# IO_Extension.net
KiCad netlist of a schematic drawn in Altium Designer
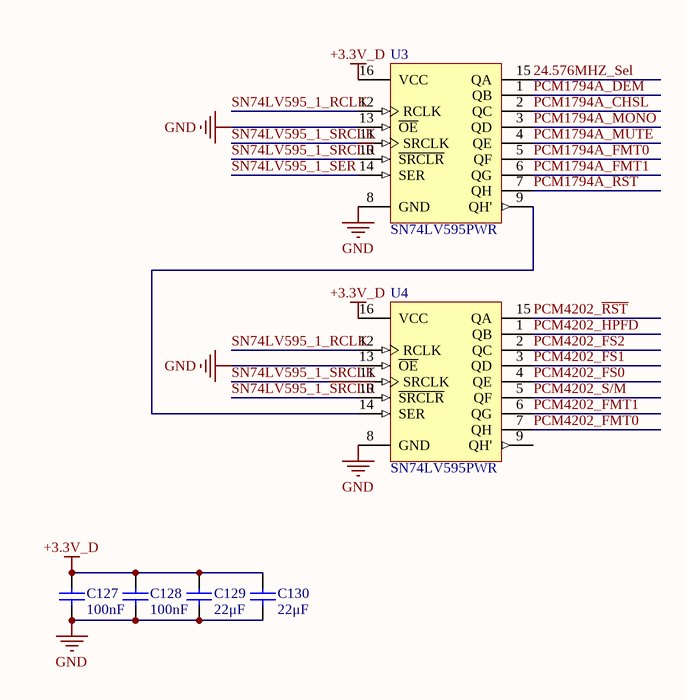
[diagram p0: IO_Extension.SchDoc]

(export (version "E")
  (design (tool "Eeschema 10.0.6"))
  (components
    (comp (ref "C127")
      (value "100nF")
      (footprint "C 0402_L")
      (description "Capacitor")
      (fields (field (name "PUBLISHER") "Altium Limited"))
      (libsource (lib "Miscellaneous Devices") (part "Cap"))
    )
    (comp (ref "C128")
      (value "100nF")
      (footprint "C 0402_L")
      (description "Capacitor")
      (fields (field (name "PUBLISHER") "Altium Limited"))
      (libsource (lib "Miscellaneous Devices") (part "Cap"))
    )
    (comp (ref "C129")
      (value "22μF")
      (footprint "0805_C")
      (description "Capacitor")
      (fields (field (name "PUBLISHER") "Altium Limited"))
      (libsource (lib "Miscellaneous Devices") (part "Cap"))
    )
    (comp (ref "C130")
      (value "22μF")
      (footprint "0805_C")
      (description "Capacitor")
      (fields (field (name "PUBLISHER") "Altium Limited"))
      (libsource (lib "Miscellaneous Devices") (part "Cap"))
    )
    (comp (ref "U3")
      (value "SN74LV595PWR")
      (footprint "PW0016A_L")
      (description "8-Bit Shift Registers With 3-State Output Registers, PW0016A, LARGE T&R")
      (fields
        (field (name "GENERIC PART NUMBER") "SN74AHC595")
        (field (name "MANUFACTURER") "Texas Instruments")
      )
      (libsource (lib "SN74LV595") (part "CMP-0807-00193-3"))
    )
    (comp (ref "U4")
      (value "SN74LV595PWR")
      (footprint "PW0016A_L")
      (description "8-Bit Shift Registers With 3-State Output Registers, PW0016A, LARGE T&R")
      (fields
        (field (name "GENERIC PART NUMBER") "SN74AHC595")
        (field (name "MANUFACTURER") "Texas Instruments")
      )
      (libsource (lib "SN74LV595") (part "CMP-0807-00193-3"))
    )
  )
  (nets
    (net (code "1") (name "+3.3V_D") (class "Default")
      (node (ref "C127") (pin "1") (pinfunction "1_1") (pintype "passive"))
      (node (ref "C128") (pin "1") (pinfunction "1_1") (pintype "passive"))
      (node (ref "C129") (pin "1") (pinfunction "1_1") (pintype "passive"))
      (node (ref "C130") (pin "1") (pinfunction "1_1") (pintype "passive"))
      (node (ref "U3") (pin "16") (pinfunction "VCC_16") (pintype "power_in"))
      (node (ref "U4") (pin "16") (pinfunction "VCC_16") (pintype "power_in"))
    )
    (net (code "2") (name "/24.576MHZ_Sel") (class "Default")
      (node (ref "U3") (pin "15") (pinfunction "QA_15") (pintype "tri_state"))
    )
    (net (code "3") (name "/PCM1794A_CHSL") (class "Default")
      (node (ref "U3") (pin "2") (pinfunction "QC_2") (pintype "tri_state"))
    )
    (net (code "4") (name "/PCM1794A_DEM") (class "Default")
      (node (ref "U3") (pin "1") (pinfunction "QB_1") (pintype "tri_state"))
    )
    (net (code "5") (name "/PCM1794A_FMT0") (class "Default")
      (node (ref "U3") (pin "5") (pinfunction "QF_5") (pintype "tri_state"))
    )
    (net (code "6") (name "/PCM1794A_FMT1") (class "Default")
      (node (ref "U3") (pin "6") (pinfunction "QG_6") (pintype "tri_state"))
    )
    (net (code "7") (name "/PCM1794A_MONO") (class "Default")
      (node (ref "U3") (pin "3") (pinfunction "QD_3") (pintype "tri_state"))
    )
    (net (code "8") (name "/PCM1794A_MUTE") (class "Default")
      (node (ref "U3") (pin "4") (pinfunction "QE_4") (pintype "tri_state"))
    )
    (net (code "9") (name "/PCM1794A_~{RST}") (class "Default")
      (node (ref "U3") (pin "7") (pinfunction "QH_7") (pintype "tri_state"))
    )
    (net (code "10") (name "/PCM4202_FMT0") (class "Default")
      (node (ref "U4") (pin "7") (pinfunction "QH_7") (pintype "tri_state"))
    )
    (net (code "11") (name "/PCM4202_FMT1") (class "Default")
      (node (ref "U4") (pin "6") (pinfunction "QG_6") (pintype "tri_state"))
    )
    (net (code "12") (name "/PCM4202_FS0") (class "Default")
      (node (ref "U4") (pin "4") (pinfunction "QE_4") (pintype "tri_state"))
    )
    (net (code "13") (name "/PCM4202_FS1") (class "Default")
      (node (ref "U4") (pin "3") (pinfunction "QD_3") (pintype "tri_state"))
    )
    (net (code "14") (name "/PCM4202_FS2") (class "Default")
      (node (ref "U4") (pin "2") (pinfunction "QC_2") (pintype "tri_state"))
    )
    (net (code "15") (name "/PCM4202_HPFD") (class "Default")
      (node (ref "U4") (pin "1") (pinfunction "QB_1") (pintype "tri_state"))
    )
    (net (code "16") (name "/PCM4202_S{slash}~{M}") (class "Default")
      (node (ref "U4") (pin "5") (pinfunction "QF_5") (pintype "tri_state"))
    )
    (net (code "17") (name "/PCM4202_~{RST}") (class "Default")
      (node (ref "U4") (pin "15") (pinfunction "QA_15") (pintype "tri_state"))
    )
    (net (code "18") (name "/SN74LV595_1_RCLK") (class "Default")
      (node (ref "U3") (pin "12") (pinfunction "RCLK_12") (pintype "input"))
      (node (ref "U4") (pin "12") (pinfunction "RCLK_12") (pintype "input"))
    )
    (net (code "19") (name "/SN74LV595_1_SER") (class "Default")
      (node (ref "U3") (pin "14") (pinfunction "SER_14") (pintype "input"))
    )
    (net (code "20") (name "/SN74LV595_1_SRCLK") (class "Default")
      (node (ref "U3") (pin "11") (pinfunction "SRCLK_11") (pintype "input"))
      (node (ref "U4") (pin "11") (pinfunction "SRCLK_11") (pintype "input"))
    )
    (net (code "21") (name "/SN74LV595_1_~{SRCLR}") (class "Default")
      (node (ref "U3") (pin "10") (pinfunction "~{SRCLR}_10") (pintype "input"))
      (node (ref "U4") (pin "10") (pinfunction "~{SRCLR}_10") (pintype "input"))
    )
    (net (code "22") (name "GND") (class "Default")
      (node (ref "C127") (pin "2") (pinfunction "2_2") (pintype "passive"))
      (node (ref "C128") (pin "2") (pinfunction "2_2") (pintype "passive"))
      (node (ref "C129") (pin "2") (pinfunction "2_2") (pintype "passive"))
      (node (ref "C130") (pin "2") (pinfunction "2_2") (pintype "passive"))
      (node (ref "U3") (pin "13") (pinfunction "~{OE}_13") (pintype "input"))
      (node (ref "U3") (pin "8") (pinfunction "GND_8") (pintype "power_in"))
      (node (ref "U4") (pin "13") (pinfunction "~{OE}_13") (pintype "input"))
      (node (ref "U4") (pin "8") (pinfunction "GND_8") (pintype "power_in"))
    )
    (net (code "23") (name "Net-(U3-QH')") (class "Default")
      (node (ref "U3") (pin "9") (pinfunction "QH'_9") (pintype "output"))
      (node (ref "U4") (pin "14") (pinfunction "SER_14") (pintype "input"))
    )
    (net (code "24") (name "unconnected-(U4-QH'-Pad9)") (class "Default")
      (node (ref "U4") (pin "9") (pinfunction "QH'_9") (pintype "output"))
    )
  )
)
